# 03_POWER.net
KiCad netlist of a schematic drawn in Altium Designer
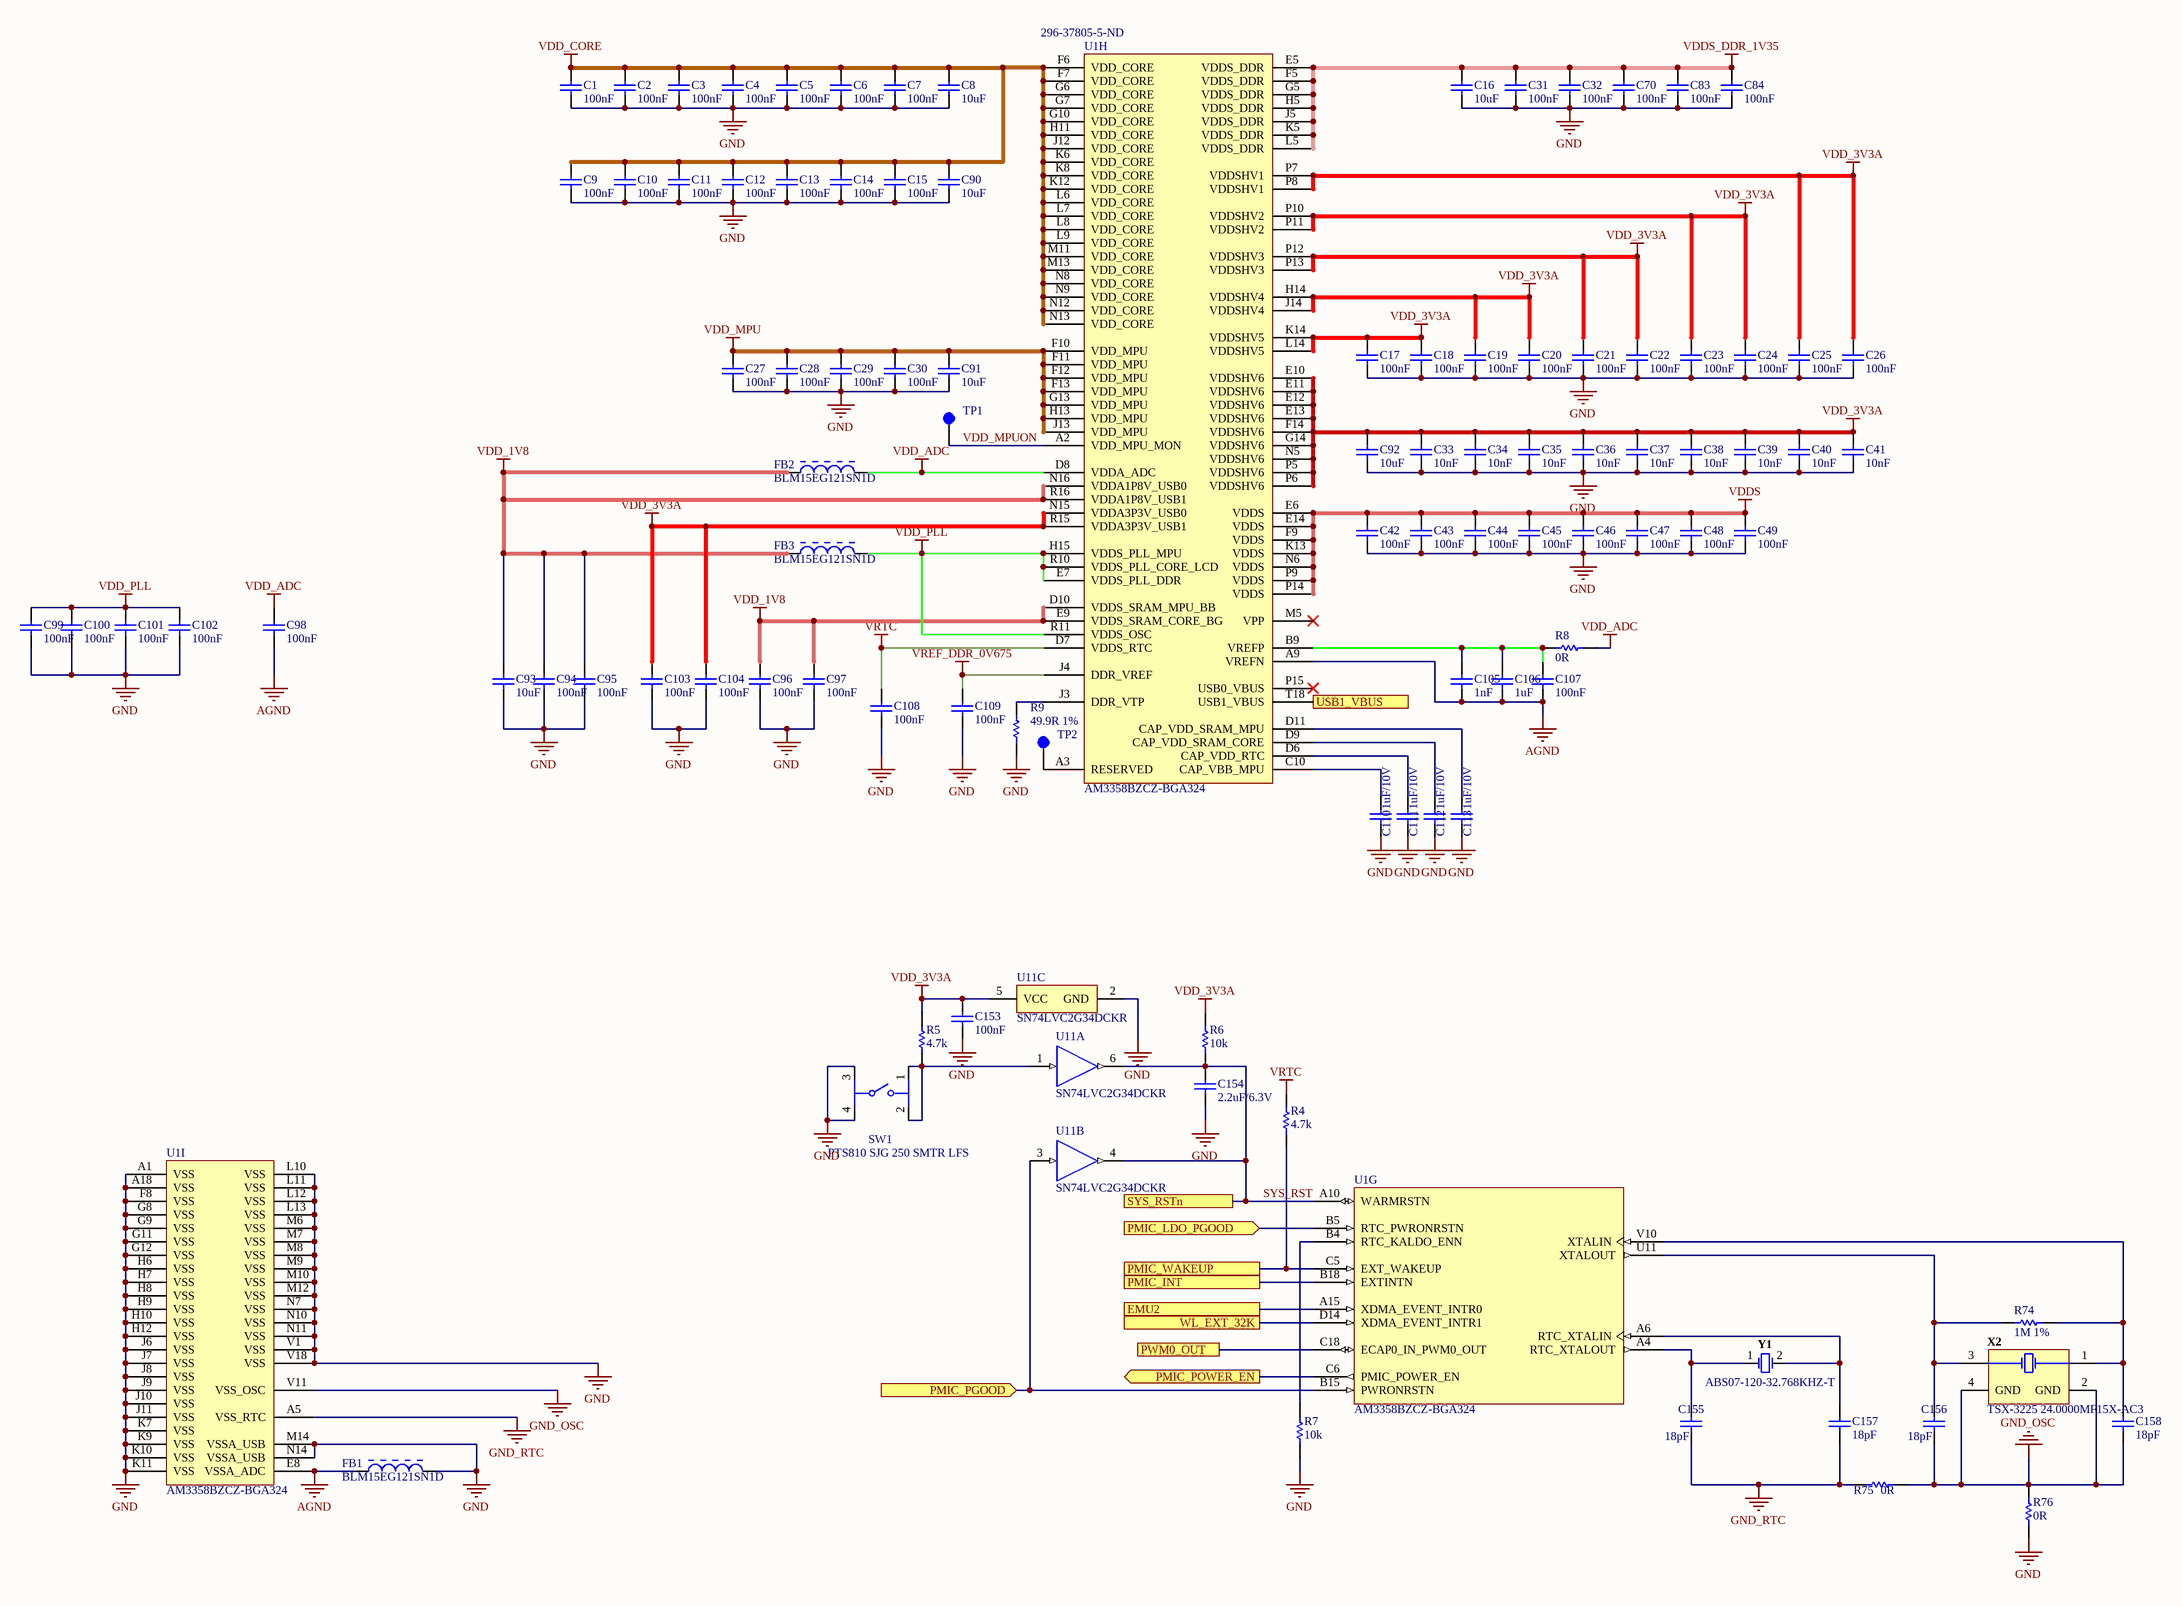
[diagram p0: 03. POWER.SchDoc]

(export (version "E")
  (design (tool "Eeschema 10.0.6"))
  (components
    (comp (ref "C1")
      (value "100nF")
      (footprint "CAPC1005X60X30LL05T10")
      (description "Chip Capacitor, 0.1 uF, +/- 10%, 16 V, -55 to 125 degC, 0402 (1005 Metric), RoHS, Tape and Reel")
      (fields (field (name "VOLTAGE") "16V") (field (name "TOLERANCE") "10%"))
      (libsource (lib "AM3358_DEV_BOARD") (part "CAP-NP-2"))
    )
    (comp (ref "C2")
      (value "100nF")
      (footprint "CAPC1005X60X30LL05T10")
      (description "Chip Capacitor, 0.1 uF, +/- 10%, 16 V, -55 to 125 degC, 0402 (1005 Metric), RoHS, Tape and Reel")
      (fields (field (name "VOLTAGE") "16V") (field (name "TOLERANCE") "10%"))
      (libsource (lib "AM3358_DEV_BOARD") (part "CAP-NP-2"))
    )
    (comp (ref "C3")
      (value "100nF")
      (footprint "CAPC1005X60X30LL05T10")
      (description "Chip Capacitor, 0.1 uF, +/- 10%, 16 V, -55 to 125 degC, 0402 (1005 Metric), RoHS, Tape and Reel")
      (fields (field (name "VOLTAGE") "16V") (field (name "TOLERANCE") "10%"))
      (libsource (lib "AM3358_DEV_BOARD") (part "CAP-NP-2"))
    )
    (comp (ref "C4")
      (value "100nF")
      (footprint "CAPC1005X60X30LL05T10")
      (description "Chip Capacitor, 0.1 uF, +/- 10%, 16 V, -55 to 125 degC, 0402 (1005 Metric), RoHS, Tape and Reel")
      (fields (field (name "VOLTAGE") "16V") (field (name "TOLERANCE") "10%"))
      (libsource (lib "AM3358_DEV_BOARD") (part "CAP-NP-2"))
    )
    (comp (ref "C5")
      (value "100nF")
      (footprint "CAPC1005X60X30LL05T10")
      (description "Chip Capacitor, 0.1 uF, +/- 10%, 16 V, -55 to 125 degC, 0402 (1005 Metric), RoHS, Tape and Reel")
      (fields (field (name "VOLTAGE") "16V") (field (name "TOLERANCE") "10%"))
      (libsource (lib "AM3358_DEV_BOARD") (part "CAP-NP-2"))
    )
    (comp (ref "C6")
      (value "100nF")
      (footprint "CAPC1005X60X30LL05T10")
      (description "Chip Capacitor, 0.1 uF, +/- 10%, 16 V, -55 to 125 degC, 0402 (1005 Metric), RoHS, Tape and Reel")
      (fields (field (name "VOLTAGE") "16V") (field (name "TOLERANCE") "10%"))
      (libsource (lib "AM3358_DEV_BOARD") (part "CAP-NP-2"))
    )
    (comp (ref "C7")
      (value "100nF")
      (footprint "CAPC1005X60X30LL05T10")
      (description "Chip Capacitor, 0.1 uF, +/- 10%, 16 V, -55 to 125 degC, 0402 (1005 Metric), RoHS, Tape and Reel")
      (fields (field (name "VOLTAGE") "16V") (field (name "TOLERANCE") "10%"))
      (libsource (lib "AM3358_DEV_BOARD") (part "CAP-NP-2"))
    )
    (comp (ref "C8")
      (value "10uF")
      (footprint "CAPC1005X60X30LL05T10")
      (fields (field (name "PART NUMBER") "GRM188R60J106ME47D") (field (name "MANUFACTURER") "Murata"))
      (libsource (lib "AM3358_DEV_BOARD") (part "CAP"))
    )
    (comp (ref "C9")
      (value "100nF")
      (footprint "CAPC1005X60X30LL05T10")
      (description "Chip Capacitor, 0.1 uF, +/- 10%, 16 V, -55 to 125 degC, 0402 (1005 Metric), RoHS, Tape and Reel")
      (fields (field (name "VOLTAGE") "16V") (field (name "TOLERANCE") "10%"))
      (libsource (lib "AM3358_DEV_BOARD") (part "CAP-NP-2"))
    )
    (comp (ref "C10")
      (value "100nF")
      (footprint "CAPC1005X60X30LL05T10")
      (description "Chip Capacitor, 0.1 uF, +/- 10%, 16 V, -55 to 125 degC, 0402 (1005 Metric), RoHS, Tape and Reel")
      (fields (field (name "VOLTAGE") "16V") (field (name "TOLERANCE") "10%"))
      (libsource (lib "AM3358_DEV_BOARD") (part "CAP-NP-2"))
    )
    (comp (ref "C11")
      (value "100nF")
      (footprint "CAPC1005X60X30LL05T10")
      (description "Chip Capacitor, 0.1 uF, +/- 10%, 16 V, -55 to 125 degC, 0402 (1005 Metric), RoHS, Tape and Reel")
      (fields (field (name "VOLTAGE") "16V") (field (name "TOLERANCE") "10%"))
      (libsource (lib "AM3358_DEV_BOARD") (part "CAP-NP-2"))
    )
    (comp (ref "C12")
      (value "100nF")
      (footprint "CAPC1005X60X30LL05T10")
      (description "Chip Capacitor, 0.1 uF, +/- 10%, 16 V, -55 to 125 degC, 0402 (1005 Metric), RoHS, Tape and Reel")
      (fields (field (name "VOLTAGE") "16V") (field (name "TOLERANCE") "10%"))
      (libsource (lib "AM3358_DEV_BOARD") (part "CAP-NP-2"))
    )
    (comp (ref "C13")
      (value "100nF")
      (footprint "CAPC1005X60X30LL05T10")
      (description "Chip Capacitor, 0.1 uF, +/- 10%, 16 V, -55 to 125 degC, 0402 (1005 Metric), RoHS, Tape and Reel")
      (fields (field (name "VOLTAGE") "16V") (field (name "TOLERANCE") "10%"))
      (libsource (lib "AM3358_DEV_BOARD") (part "CAP-NP-2"))
    )
    (comp (ref "C14")
      (value "100nF")
      (footprint "CAPC1005X60X30LL05T10")
      (description "Chip Capacitor, 0.1 uF, +/- 10%, 16 V, -55 to 125 degC, 0402 (1005 Metric), RoHS, Tape and Reel")
      (fields (field (name "VOLTAGE") "16V") (field (name "TOLERANCE") "10%"))
      (libsource (lib "AM3358_DEV_BOARD") (part "CAP-NP-2"))
    )
    (comp (ref "C15")
      (value "100nF")
      (footprint "CAPC1005X60X30LL05T10")
      (description "Chip Capacitor, 0.1 uF, +/- 10%, 16 V, -55 to 125 degC, 0402 (1005 Metric), RoHS, Tape and Reel")
      (fields (field (name "VOLTAGE") "16V") (field (name "TOLERANCE") "10%"))
      (libsource (lib "AM3358_DEV_BOARD") (part "CAP-NP-2"))
    )
    (comp (ref "C16")
      (value "10uF")
      (footprint "CAPC1608X90X35NL10T15")
      (fields (field (name "PART NUMBER") "GRM188R60J106ME47D") (field (name "MANUFACTURER") "Murata"))
      (libsource (lib "Altium Content Vault") (part "CAP"))
    )
    (comp (ref "C17")
      (value "100nF")
      (footprint "CAPC1005X60X30LL05T10")
      (description "Chip Capacitor, 0.1 uF, +/- 10%, 16 V, -55 to 125 degC, 0402 (1005 Metric), RoHS, Tape and Reel")
      (fields (field (name "VOLTAGE") "16V") (field (name "TOLERANCE") "10%"))
      (libsource (lib "AM3358_DEV_BOARD") (part "CAP-NP-2"))
    )
    (comp (ref "C18")
      (value "100nF")
      (footprint "CAPC1005X60X30LL05T10")
      (description "Chip Capacitor, 0.1 uF, +/- 10%, 16 V, -55 to 125 degC, 0402 (1005 Metric), RoHS, Tape and Reel")
      (fields (field (name "VOLTAGE") "16V") (field (name "TOLERANCE") "10%"))
      (libsource (lib "AM3358_DEV_BOARD") (part "CAP-NP-2"))
    )
    (comp (ref "C19")
      (value "100nF")
      (footprint "CAPC1005X60X30LL05T10")
      (description "Chip Capacitor, 0.1 uF, +/- 10%, 16 V, -55 to 125 degC, 0402 (1005 Metric), RoHS, Tape and Reel")
      (fields (field (name "VOLTAGE") "16V") (field (name "TOLERANCE") "10%"))
      (libsource (lib "AM3358_DEV_BOARD") (part "CAP-NP-2"))
    )
    (comp (ref "C20")
      (value "100nF")
      (footprint "CAPC1005X60X30LL05T10")
      (description "Chip Capacitor, 0.1 uF, +/- 10%, 16 V, -55 to 125 degC, 0402 (1005 Metric), RoHS, Tape and Reel")
      (fields (field (name "VOLTAGE") "16V") (field (name "TOLERANCE") "10%"))
      (libsource (lib "AM3358_DEV_BOARD") (part "CAP-NP-2"))
    )
    (comp (ref "C21")
      (value "100nF")
      (footprint "CAPC1005X60X30LL05T10")
      (description "Chip Capacitor, 0.1 uF, +/- 10%, 16 V, -55 to 125 degC, 0402 (1005 Metric), RoHS, Tape and Reel")
      (fields (field (name "VOLTAGE") "16V") (field (name "TOLERANCE") "10%"))
      (libsource (lib "AM3358_DEV_BOARD") (part "CAP-NP-2"))
    )
    (comp (ref "C22")
      (value "100nF")
      (footprint "CAPC1005X60X30LL05T10")
      (description "Chip Capacitor, 0.1 uF, +/- 10%, 16 V, -55 to 125 degC, 0402 (1005 Metric), RoHS, Tape and Reel")
      (fields (field (name "VOLTAGE") "16V") (field (name "TOLERANCE") "10%"))
      (libsource (lib "AM3358_DEV_BOARD") (part "CAP-NP-2"))
    )
    (comp (ref "C23")
      (value "100nF")
      (footprint "CAPC1005X60X30LL05T10")
      (description "Chip Capacitor, 0.1 uF, +/- 10%, 16 V, -55 to 125 degC, 0402 (1005 Metric), RoHS, Tape and Reel")
      (fields (field (name "VOLTAGE") "16V") (field (name "TOLERANCE") "10%"))
      (libsource (lib "AM3358_DEV_BOARD") (part "CAP-NP-2"))
    )
    (comp (ref "C24")
      (value "100nF")
      (footprint "CAPC1005X60X30LL05T10")
      (description "Chip Capacitor, 0.1 uF, +/- 10%, 16 V, -55 to 125 degC, 0402 (1005 Metric), RoHS, Tape and Reel")
      (fields (field (name "VOLTAGE") "16V") (field (name "TOLERANCE") "10%"))
      (libsource (lib "AM3358_DEV_BOARD") (part "CAP-NP-2"))
    )
    (comp (ref "C25")
      (value "100nF")
      (footprint "CAPC1005X60X30LL05T10")
      (description "Chip Capacitor, 0.1 uF, +/- 10%, 16 V, -55 to 125 degC, 0402 (1005 Metric), RoHS, Tape and Reel")
      (fields (field (name "VOLTAGE") "16V") (field (name "TOLERANCE") "10%"))
      (libsource (lib "AM3358_DEV_BOARD") (part "CAP-NP-2"))
    )
    (comp (ref "C26")
      (value "100nF")
      (footprint "CAPC1005X60X30LL05T10")
      (description "Chip Capacitor, 0.1 uF, +/- 10%, 16 V, -55 to 125 degC, 0402 (1005 Metric), RoHS, Tape and Reel")
      (fields (field (name "VOLTAGE") "16V") (field (name "TOLERANCE") "10%"))
      (libsource (lib "AM3358_DEV_BOARD") (part "CAP-NP-2"))
    )
    (comp (ref "C27")
      (value "100nF")
      (footprint "CAPC1005X60X30LL05T10")
      (description "Chip Capacitor, 0.1 uF, +/- 10%, 16 V, -55 to 125 degC, 0402 (1005 Metric), RoHS, Tape and Reel")
      (fields (field (name "VOLTAGE") "16V") (field (name "TOLERANCE") "10%"))
      (libsource (lib "AM3358_DEV_BOARD") (part "CAP-NP-2"))
    )
    (comp (ref "C28")
      (value "100nF")
      (footprint "CAPC1005X60X30LL05T10")
      (description "Chip Capacitor, 0.1 uF, +/- 10%, 16 V, -55 to 125 degC, 0402 (1005 Metric), RoHS, Tape and Reel")
      (fields (field (name "VOLTAGE") "16V") (field (name "TOLERANCE") "10%"))
      (libsource (lib "AM3358_DEV_BOARD") (part "CAP-NP-2"))
    )
    (comp (ref "C29")
      (value "100nF")
      (footprint "CAPC1005X60X30LL05T10")
      (description "Chip Capacitor, 0.1 uF, +/- 10%, 16 V, -55 to 125 degC, 0402 (1005 Metric), RoHS, Tape and Reel")
      (fields (field (name "VOLTAGE") "16V") (field (name "TOLERANCE") "10%"))
      (libsource (lib "AM3358_DEV_BOARD") (part "CAP-NP-2"))
    )
    (comp (ref "C30")
      (value "100nF")
      (footprint "CAPC1005X60X30LL05T10")
      (description "Chip Capacitor, 0.1 uF, +/- 10%, 16 V, -55 to 125 degC, 0402 (1005 Metric), RoHS, Tape and Reel")
      (fields (field (name "VOLTAGE") "16V") (field (name "TOLERANCE") "10%"))
      (libsource (lib "AM3358_DEV_BOARD") (part "CAP-NP-2"))
    )
    (comp (ref "C31")
      (value "100nF")
      (footprint "CAPC1005X60X30LL05T10")
      (description "Chip Capacitor, 0.1 uF, +/- 10%, 16 V, -55 to 125 degC, 0402 (1005 Metric), RoHS, Tape and Reel")
      (fields (field (name "VOLTAGE") "16V") (field (name "TOLERANCE") "10%"))
      (libsource (lib "AM3358_DEV_BOARD") (part "CAP-NP-2"))
    )
    (comp (ref "C32")
      (value "100nF")
      (footprint "CAPC1005X60X30LL05T10")
      (description "Chip Capacitor, 0.1 uF, +/- 10%, 16 V, -55 to 125 degC, 0402 (1005 Metric), RoHS, Tape and Reel")
      (fields (field (name "VOLTAGE") "16V") (field (name "TOLERANCE") "10%"))
      (libsource (lib "AM3358_DEV_BOARD") (part "CAP-NP-2"))
    )
    (comp (ref "C33")
      (value "10nF")
      (footprint "CAPC1005X60X30LL05T10")
      (description "Chip Capacitor, 0.1 uF, +/- 10%, 16 V, -55 to 125 degC, 0402 (1005 Metric), RoHS, Tape and Reel")
      (fields (field (name "VOLTAGE") "16V") (field (name "TOLERANCE") "10%"))
      (libsource (lib "AM3358_DEV_BOARD") (part "CAP-NP-2"))
    )
    (comp (ref "C34")
      (value "10nF")
      (footprint "CAPC1005X60X30LL05T10")
      (description "Chip Capacitor, 0.1 uF, +/- 10%, 16 V, -55 to 125 degC, 0402 (1005 Metric), RoHS, Tape and Reel")
      (fields (field (name "VOLTAGE") "16V") (field (name "TOLERANCE") "10%"))
      (libsource (lib "AM3358_DEV_BOARD") (part "CAP-NP-2"))
    )
    (comp (ref "C35")
      (value "10nF")
      (footprint "CAPC1005X60X30LL05T10")
      (description "Chip Capacitor, 0.1 uF, +/- 10%, 16 V, -55 to 125 degC, 0402 (1005 Metric), RoHS, Tape and Reel")
      (fields (field (name "VOLTAGE") "16V") (field (name "TOLERANCE") "10%"))
      (libsource (lib "AM3358_DEV_BOARD") (part "CAP-NP-2"))
    )
    (comp (ref "C36")
      (value "10nF")
      (footprint "CAPC1005X60X30LL05T10")
      (description "Chip Capacitor, 0.1 uF, +/- 10%, 16 V, -55 to 125 degC, 0402 (1005 Metric), RoHS, Tape and Reel")
      (fields (field (name "VOLTAGE") "16V") (field (name "TOLERANCE") "10%"))
      (libsource (lib "AM3358_DEV_BOARD") (part "CAP-NP-2"))
    )
    (comp (ref "C37")
      (value "10nF")
      (footprint "CAPC1005X60X30LL05T10")
      (description "Chip Capacitor, 0.1 uF, +/- 10%, 16 V, -55 to 125 degC, 0402 (1005 Metric), RoHS, Tape and Reel")
      (fields (field (name "VOLTAGE") "16V") (field (name "TOLERANCE") "10%"))
      (libsource (lib "AM3358_DEV_BOARD") (part "CAP-NP-2"))
    )
    (comp (ref "C38")
      (value "10nF")
      (footprint "CAPC1005X60X30LL05T10")
      (description "Chip Capacitor, 0.1 uF, +/- 10%, 16 V, -55 to 125 degC, 0402 (1005 Metric), RoHS, Tape and Reel")
      (fields (field (name "VOLTAGE") "16V") (field (name "TOLERANCE") "10%"))
      (libsource (lib "AM3358_DEV_BOARD") (part "CAP-NP-2"))
    )
    (comp (ref "C39")
      (value "10nF")
      (footprint "CAPC1005X60X30LL05T10")
      (description "Chip Capacitor, 0.1 uF, +/- 10%, 16 V, -55 to 125 degC, 0402 (1005 Metric), RoHS, Tape and Reel")
      (fields (field (name "VOLTAGE") "16V") (field (name "TOLERANCE") "10%"))
      (libsource (lib "AM3358_DEV_BOARD") (part "CAP-NP-2"))
    )
    (comp (ref "C40")
      (value "10nF")
      (footprint "CAPC1005X60X30LL05T10")
      (description "Chip Capacitor, 0.1 uF, +/- 10%, 16 V, -55 to 125 degC, 0402 (1005 Metric), RoHS, Tape and Reel")
      (fields (field (name "VOLTAGE") "16V") (field (name "TOLERANCE") "10%"))
      (libsource (lib "AM3358_DEV_BOARD") (part "CAP-NP-2"))
    )
    (comp (ref "C41")
      (value "10nF")
      (footprint "CAPC1005X60X30LL05T10")
      (description "Chip Capacitor, 0.1 uF, +/- 10%, 16 V, -55 to 125 degC, 0402 (1005 Metric), RoHS, Tape and Reel")
      (fields (field (name "VOLTAGE") "16V") (field (name "TOLERANCE") "10%"))
      (libsource (lib "AM3358_DEV_BOARD") (part "CAP-NP-2"))
    )
    (comp (ref "C42")
      (value "100nF")
      (footprint "CAPC1005X60X30LL05T10")
      (description "Chip Capacitor, 0.1 uF, +/- 10%, 16 V, -55 to 125 degC, 0402 (1005 Metric), RoHS, Tape and Reel")
      (fields (field (name "VOLTAGE") "16V") (field (name "TOLERANCE") "10%"))
      (libsource (lib "AM3358_DEV_BOARD") (part "CAP-NP-2"))
    )
    (comp (ref "C43")
      (value "100nF")
      (footprint "CAPC1005X60X30LL05T10")
      (description "Chip Capacitor, 0.1 uF, +/- 10%, 16 V, -55 to 125 degC, 0402 (1005 Metric), RoHS, Tape and Reel")
      (fields (field (name "VOLTAGE") "16V") (field (name "TOLERANCE") "10%"))
      (libsource (lib "AM3358_DEV_BOARD") (part "CAP-NP-2"))
    )
    (comp (ref "C44")
      (value "100nF")
      (footprint "CAPC1005X60X30LL05T10")
      (description "Chip Capacitor, 0.1 uF, +/- 10%, 16 V, -55 to 125 degC, 0402 (1005 Metric), RoHS, Tape and Reel")
      (fields (field (name "VOLTAGE") "16V") (field (name "TOLERANCE") "10%"))
      (libsource (lib "AM3358_DEV_BOARD") (part "CAP-NP-2"))
    )
    (comp (ref "C45")
      (value "100nF")
      (footprint "CAPC1005X60X30LL05T10")
      (description "Chip Capacitor, 0.1 uF, +/- 10%, 16 V, -55 to 125 degC, 0402 (1005 Metric), RoHS, Tape and Reel")
      (fields (field (name "VOLTAGE") "16V") (field (name "TOLERANCE") "10%"))
      (libsource (lib "AM3358_DEV_BOARD") (part "CAP-NP-2"))
    )
    (comp (ref "C46")
      (value "100nF")
      (footprint "CAPC1005X60X30LL05T10")
      (description "Chip Capacitor, 0.1 uF, +/- 10%, 16 V, -55 to 125 degC, 0402 (1005 Metric), RoHS, Tape and Reel")
      (fields (field (name "VOLTAGE") "16V") (field (name "TOLERANCE") "10%"))
      (libsource (lib "AM3358_DEV_BOARD") (part "CAP-NP-2"))
    )
    (comp (ref "C47")
      (value "100nF")
      (footprint "CAPC1005X60X30LL05T10")
      (description "Chip Capacitor, 0.1 uF, +/- 10%, 16 V, -55 to 125 degC, 0402 (1005 Metric), RoHS, Tape and Reel")
      (fields (field (name "VOLTAGE") "16V") (field (name "TOLERANCE") "10%"))
      (libsource (lib "AM3358_DEV_BOARD") (part "CAP-NP-2"))
    )
    (comp (ref "C48")
      (value "100nF")
      (footprint "CAPC1005X60X30LL05T10")
      (description "Chip Capacitor, 0.1 uF, +/- 10%, 16 V, -55 to 125 degC, 0402 (1005 Metric), RoHS, Tape and Reel")
      (fields (field (name "VOLTAGE") "16V") (field (name "TOLERANCE") "10%"))
      (libsource (lib "AM3358_DEV_BOARD") (part "CAP-NP-2"))
    )
    (comp (ref "C49")
      (value "100nF")
      (footprint "CAPC1005X60X30LL05T10")
      (description "Chip Capacitor, 0.1 uF, +/- 10%, 16 V, -55 to 125 degC, 0402 (1005 Metric), RoHS, Tape and Reel")
      (fields (field (name "VOLTAGE") "16V") (field (name "TOLERANCE") "10%"))
      (libsource (lib "AM3358_DEV_BOARD") (part "CAP-NP-2"))
    )
    (comp (ref "C70")
      (value "100nF")
      (footprint "CAPC1005X60X30LL05T10")
      (description "Chip Capacitor, 0.1 uF, +/- 10%, 16 V, -55 to 125 degC, 0402 (1005 Metric), RoHS, Tape and Reel")
      (fields (field (name "VOLTAGE") "16V") (field (name "TOLERANCE") "10%"))
      (libsource (lib "AM3358_DEV_BOARD") (part "CAP-NP-2"))
    )
    (comp (ref "C83")
      (value "100nF")
      (footprint "CAPC1005X60X30LL05T10")
      (description "Chip Capacitor, 0.1 uF, +/- 10%, 16 V, -55 to 125 degC, 0402 (1005 Metric), RoHS, Tape and Reel")
      (fields (field (name "VOLTAGE") "16V") (field (name "TOLERANCE") "10%"))
      (libsource (lib "AM3358_DEV_BOARD") (part "CAP-NP-2"))
    )
    (comp (ref "C84")
      (value "100nF")
      (footprint "CAPC1005X60X30LL05T10")
      (description "Chip Capacitor, 0.1 uF, +/- 10%, 16 V, -55 to 125 degC, 0402 (1005 Metric), RoHS, Tape and Reel")
      (fields (field (name "VOLTAGE") "16V") (field (name "TOLERANCE") "10%"))
      (libsource (lib "AM3358_DEV_BOARD") (part "CAP-NP-2"))
    )
    (comp (ref "C90")
      (value "10uF")
      (footprint "CAPC1005X60X30LL05T10")
      (fields (field (name "PART NUMBER") "GRM188R60J106ME47D") (field (name "MANUFACTURER") "Murata"))
      (libsource (lib "AM3358_DEV_BOARD") (part "CAP"))
    )
    (comp (ref "C91")
      (value "10uF")
      (footprint "RESC1005X40X25LL05T05")
      (fields (field (name "PART NUMBER") "GRM188R60J106ME47D") (field (name "MANUFACTURER") "Murata"))
      (libsource (lib "AM3358_DEV_BOARD") (part "CAP"))
    )
    (comp (ref "C92")
      (value "10uF")
      (footprint "CAPC1608X90X35NL10T15")
      (fields (field (name "PART NUMBER") "GRM188R60J106ME47D") (field (name "MANUFACTURER") "Murata"))
      (libsource (lib "Altium Content Vault") (part "CAP"))
    )
    (comp (ref "C93")
      (value "10uF")
      (footprint "CAPC1608X90X35NL10T15")
      (fields (field (name "PART NUMBER") "GRM188R60J106ME47D") (field (name "MANUFACTURER") "Murata"))
      (libsource (lib "Altium Content Vault") (part "CAP"))
    )
    (comp (ref "C94")
      (value "100nF")
      (footprint "CAPC1005X60X30LL05T10")
      (description "Chip Capacitor, 0.1 uF, +/- 10%, 16 V, -55 to 125 degC, 0402 (1005 Metric), RoHS, Tape and Reel")
      (fields (field (name "VOLTAGE") "16V") (field (name "TOLERANCE") "10%"))
      (libsource (lib "AM3358_DEV_BOARD") (part "CAP-NP-2"))
    )
    (comp (ref "C95")
      (value "100nF")
      (footprint "CAPC1005X60X30LL05T10")
      (description "Chip Capacitor, 0.1 uF, +/- 10%, 16 V, -55 to 125 degC, 0402 (1005 Metric), RoHS, Tape and Reel")
      (fields (field (name "VOLTAGE") "16V") (field (name "TOLERANCE") "10%"))
      (libsource (lib "AM3358_DEV_BOARD") (part "CAP-NP-2"))
    )
    (comp (ref "C96")
      (value "100nF")
      (footprint "CAPC1005X60X30LL05T10")
      (description "Chip Capacitor, 0.1 uF, +/- 10%, 16 V, -55 to 125 degC, 0402 (1005 Metric), RoHS, Tape and Reel")
      (fields (field (name "VOLTAGE") "16V") (field (name "TOLERANCE") "10%"))
      (libsource (lib "AM3358_DEV_BOARD") (part "CAP-NP-2"))
    )
    (comp (ref "C97")
      (value "100nF")
      (footprint "CAPC1005X60X30LL05T10")
      (description "Chip Capacitor, 0.1 uF, +/- 10%, 16 V, -55 to 125 degC, 0402 (1005 Metric), RoHS, Tape and Reel")
      (fields (field (name "VOLTAGE") "16V") (field (name "TOLERANCE") "10%"))
      (libsource (lib "AM3358_DEV_BOARD") (part "CAP-NP-2"))
    )
    (comp (ref "C98")
      (value "100nF")
      (footprint "RESC1005X40X25LL05T05")
      (description "Chip Capacitor, 0.1 uF, +/- 10%, 16 V, -55 to 125 degC, 0402 (1005 Metric), RoHS, Tape and Reel")
      (fields (field (name "VOLTAGE") "16V") (field (name "TOLERANCE") "10%"))
      (libsource (lib "AM3358_DEV_BOARD") (part "CAP-NP-2"))
    )
    (comp (ref "C99")
      (value "100nF")
      (footprint "RESC1005X40X25LL05T05")
      (description "Chip Capacitor, 0.1 uF, +/- 10%, 16 V, -55 to 125 degC, 0402 (1005 Metric), RoHS, Tape and Reel")
      (fields (field (name "VOLTAGE") "16V") (field (name "TOLERANCE") "10%"))
      (libsource (lib "AM3358_DEV_BOARD") (part "CAP-NP-2"))
    )
    (comp (ref "C100")
      (value "100nF")
      (footprint "RESC1005X40X25LL05T05")
      (description "Chip Capacitor, 0.1 uF, +/- 10%, 16 V, -55 to 125 degC, 0402 (1005 Metric), RoHS, Tape and Reel")
      (fields (field (name "VOLTAGE") "16V") (field (name "TOLERANCE") "10%"))
      (libsource (lib "AM3358_DEV_BOARD") (part "CAP-NP-2"))
    )
    (comp (ref "C101")
      (value "100nF")
      (footprint "RESC1005X40X25LL05T05")
      (description "Chip Capacitor, 0.1 uF, +/- 10%, 16 V, -55 to 125 degC, 0402 (1005 Metric), RoHS, Tape and Reel")
      (fields (field (name "VOLTAGE") "16V") (field (name "TOLERANCE") "10%"))
      (libsource (lib "AM3358_DEV_BOARD") (part "CAP-NP-2"))
    )
    (comp (ref "C102")
      (value "100nF")
      (footprint "RESC1005X40X25LL05T05")
      (description "Chip Capacitor, 0.1 uF, +/- 10%, 16 V, -55 to 125 degC, 0402 (1005 Metric), RoHS, Tape and Reel")
      (fields (field (name "VOLTAGE") "16V") (field (name "TOLERANCE") "10%"))
      (libsource (lib "AM3358_DEV_BOARD") (part "CAP-NP-2"))
    )
    (comp (ref "C103")
      (value "100nF")
      (footprint "CAPC1005X60X30LL05T10")
      (description "Chip Capacitor, 0.1 uF, +/- 10%, 16 V, -55 to 125 degC, 0402 (1005 Metric), RoHS, Tape and Reel")
      (fields (field (name "VOLTAGE") "16V") (field (name "TOLERANCE") "10%"))
      (libsource (lib "AM3358_DEV_BOARD") (part "CAP-NP-2"))
    )
    (comp (ref "C104")
      (value "100nF")
      (footprint "CAPC1005X60X30LL05T10")
      (description "Chip Capacitor, 0.1 uF, +/- 10%, 16 V, -55 to 125 degC, 0402 (1005 Metric), RoHS, Tape and Reel")
      (fields (field (name "VOLTAGE") "16V") (field (name "TOLERANCE") "10%"))
      (libsource (lib "AM3358_DEV_BOARD") (part "CAP-NP-2"))
    )
    (comp (ref "C105")
      (value "1nF")
      (footprint "CAPC1005X60X30LL05T10")
      (fields (field (name "PART NUMBER") "GRM1555C1H102JA01D") (field (name "MANUFACTURER") "Murata"))
      (libsource (lib "AM3358_DEV_BOARD") (part "CAP"))
    )
    (comp (ref "C106")
      (value "1uF")
      (footprint "CAPC1005X55X25NL05T10")
      (fields (field (name "PART NUMBER") "GRM155R61A105KE15D") (field (name "MANUFACTURER") "Murata"))
      (libsource (lib "Altium Content Vault") (part "CAP"))
    )
    (comp (ref "C107")
      (value "100nF")
      (footprint "CAPC1005X60X30LL05T10")
      (description "Chip Capacitor, 0.1 uF, +/- 10%, 16 V, -55 to 125 degC, 0402 (1005 Metric), RoHS, Tape and Reel")
      (fields (field (name "VOLTAGE") "16V") (field (name "TOLERANCE") "10%"))
      (libsource (lib "AM3358_DEV_BOARD") (part "CAP-NP-2"))
    )
    (comp (ref "C108")
      (value "100nF")
      (footprint "CAPC1005X60X30LL05T10")
      (description "Chip Capacitor, 0.1 uF, +/- 10%, 16 V, -55 to 125 degC, 0402 (1005 Metric), RoHS, Tape and Reel")
      (fields (field (name "VOLTAGE") "16V") (field (name "TOLERANCE") "10%"))
      (libsource (lib "AM3358_DEV_BOARD") (part "CAP-NP-2"))
    )
    (comp (ref "C109")
      (value "100nF")
      (footprint "CAPC1005X60X30LL05T10")
      (description "Chip Capacitor, 0.1 uF, +/- 10%, 16 V, -55 to 125 degC, 0402 (1005 Metric), RoHS, Tape and Reel")
      (fields (field (name "VOLTAGE") "16V") (field (name "TOLERANCE") "10%"))
      (libsource (lib "AM3358_DEV_BOARD") (part "CAP-NP-2"))
    )
    (comp (ref "C110")
      (value "1uF/10V")
      (footprint "CAPC1005X55X25NL05T10")
      (fields (field (name "PART NUMBER") "GRM155R61A105KE15D") (field (name "MANUFACTURER") "Murata"))
      (libsource (lib "Altium Content Vault") (part "CAP"))
    )
    (comp (ref "C111")
      (value "1uF/10V")
      (footprint "CAPC1005X55X25NL05T10")
      (fields (field (name "PART NUMBER") "GRM155R61A105KE15D") (field (name "MANUFACTURER") "Murata"))
      (libsource (lib "Altium Content Vault") (part "CAP"))
    )
    (comp (ref "C112")
      (value "1uF/10V")
      (footprint "CAPC1005X55X25NL05T10")
      (fields (field (name "PART NUMBER") "GRM155R61A105KE15D") (field (name "MANUFACTURER") "Murata"))
      (libsource (lib "Altium Content Vault") (part "CAP"))
    )
    (comp (ref "C113")
      (value "1uF/10V")
      (footprint "CAPC1005X55X25NL05T10")
      (fields (field (name "PART NUMBER") "GRM155R61A105KE15D") (field (name "MANUFACTURER") "Murata"))
      (libsource (lib "Altium Content Vault") (part "CAP"))
    )
    (comp (ref "C153")
      (value "100nF")
      (footprint "CAPC1005X55X25LL05T10")
      (description "Chip Capacitor, 0.1 uF, +/- 10%, 16 V, -55 to 125 degC, 0402 (1005 Metric), RoHS, Tape and Reel")
      (fields (field (name "VOLTAGE") "16V") (field (name "TOLERANCE") "10%"))
      (libsource (lib "Altium Content Vault") (part "CAP-NP-2"))
    )
    (comp (ref "C154")
      (value "2.2uF/6.3V")
      (footprint "CAPC1005X60X30LL05T10")
      (fields (field (name "MANUFACTURER") "Kemet") (field (name "PART NUMBER") "C0402C225M9PAC7867"))
      (libsource (lib "Altium Content Vault") (part "CAP"))
    )
    (comp (ref "C155")
      (value "18pF")
      (footprint "CAPC1005X60X30LL05T10")
      (fields (field (name "PART NUMBER") "GRM1555C1H180JA01D") (field (name "MANUFACTURER") "Murata"))
      (libsource (lib "AM3358_DEV_BOARD") (part "CAP"))
    )
    (comp (ref "C156")
      (value "18pF")
      (footprint "CAPC1005X60X30LL05T10")
      (fields (field (name "PART NUMBER") "GRM1555C1H180JA01D") (field (name "MANUFACTURER") "Murata"))
      (libsource (lib "AM3358_DEV_BOARD") (part "CAP"))
    )
    (comp (ref "C157")
      (value "18pF")
      (footprint "CAPC1005X60X30LL05T10")
      (fields (field (name "PART NUMBER") "GRM1555C1H180JA01D") (field (name "MANUFACTURER") "Murata"))
      (libsource (lib "AM3358_DEV_BOARD") (part "CAP"))
    )
    (comp (ref "C158")
      (value "18pF")
      (footprint "CAPC1005X60X30LL05T10")
      (fields (field (name "PART NUMBER") "GRM1555C1H180JA01D") (field (name "MANUFACTURER") "Murata"))
      (libsource (lib "AM3358_DEV_BOARD") (part "CAP"))
    )
    (comp (ref "FB1")
      (value "BLM15EG121SN1D")
      (footprint "MURA-BLM15-CHIP-2_V")
      (fields (field (name "MANUFACTURER") "Murata"))
      (libsource (lib "Altium Content Vault") (part "MURA-FB-2"))
    )
    (comp (ref "FB2")
      (value "BLM15EG121SN1D")
      (footprint "MURA-BLM15-CHIP-2_V")
      (fields (field (name "MANUFACTURER") "Murata"))
      (libsource (lib "Altium Content Vault") (part "MURA-FB-2"))
    )
    (comp (ref "FB3")
      (value "BLM15EG121SN1D")
      (footprint "MURA-BLM15-CHIP-2_V")
      (fields (field (name "MANUFACTURER") "Murata"))
      (libsource (lib "Altium Content Vault") (part "MURA-FB-2"))
    )
    (comp (ref "R4")
      (value "4.7k")
      (footprint "RESC1005X40X25LL05T05")
      (fields (field (name "PART NUMBER") "RC0402FR-134K7L") (field (name "MANUFACTURER") "Yageo"))
      (libsource (lib "AM3358_DEV_BOARD") (part "RES"))
    )
    (comp (ref "R5")
      (value "4.7k")
      (footprint "RESC1005X40X25LL05T05")
      (fields (field (name "PART NUMBER") "RC0402FR-134K7L") (field (name "MANUFACTURER") "Yageo"))
      (libsource (lib "AM3358_DEV_BOARD") (part "RES"))
    )
    (comp (ref "R6")
      (value "10k")
      (footprint "RESC1005X40X25LL05T05")
      (fields (field (name "MANUFACTURER") "Vishay Dale") (field (name "PART NUMBER") "CRCW040210K0FKED"))
      (libsource (lib "AM3358_DEV_BOARD") (part "RES"))
    )
    (comp (ref "R7")
      (value "10k")
      (footprint "RESC1005X40X25LL05T05")
      (fields (field (name "MANUFACTURER") "Vishay Dale") (field (name "PART NUMBER") "CRCW040210K0FKED"))
      (libsource (lib "AM3358_DEV_BOARD") (part "RES"))
    )
    (comp (ref "R8")
      (value "0R")
      (footprint "RESC1005X40X25LL05T05")
      (fields (field (name "MANUFACTURER") "Yageo / Phycomp") (field (name "PART NUMBER") "RC0402JR-070RL"))
      (libsource (lib "AM3358_DEV_BOARD") (part "RES"))
    )
    (comp (ref "R9")
      (value "49.9R 1%")
      (footprint "RESC1005X40X25LL05T05")
      (description "Precision Thick Film Chip Resistors")
      (fields (field (name "MANUFACTURER") "Panasonic") (field (name "PART NUMBER") "ERJ-2RKF49R9X"))
      (libsource (lib "AM3358_DEV_BOARD") (part "RES"))
    )
    (comp (ref "R74")
      (value "1M 1%")
      (footprint "RESC1005X40X25LL05T05")
      (description "Chip Resistor, 1 MOhm, +/- 1%, 100 mW, -55 to 155 degC, 0402 (1005 Metric), RoHS, Tape and Reel")
      (fields (field (name "PARTNUMBER") "ERJ-2RKF1004X") (field (name "TOLERANCE") "1%"))
      (libsource (lib "AM3358_DEV_BOARD") (part "RES-2"))
    )
    (comp (ref "R75")
      (value "0R")
      (footprint "RESC1005X40X25LL05T05")
      (fields (field (name "MANUFACTURER") "Yageo / Phycomp") (field (name "PART NUMBER") "RC0402JR-070RL"))
      (libsource (lib "AM3358_DEV_BOARD") (part "RES"))
    )
    (comp (ref "R76")
      (value "0R")
      (footprint "RESC1005X40X25LL05T05")
      (fields (field (name "MANUFACTURER") "Yageo / Phycomp") (field (name "PART NUMBER") "RC0402JR-070RL"))
      (libsource (lib "AM3358_DEV_BOARD") (part "RES"))
    )
    (comp (ref "SW1")
      (value "PTS810 SJG 250 SMTR LFS")
      (footprint "FP-PTS810_SJG_250_SMTR_LF-MFG")
      (description "SWITCH TACTILE SPST-NO 0.05A 16V")
      (fields
        (field (name "MANUFACTURER") "C&K Components")
        (field (name "OCTOPART") "https://octopart.com/pts810sjg250smtrlfs-c%26k+components-29380277")
      )
      (libsource (lib "Altium Content Vault") (part "1adf0dd01260c80cf25a44bfd6b99ba"))
    )
    (comp (ref "TP1") (value "Test Point") (footprint "TP") (libsource (lib "SyTungNguyen") (part "TP")))
    (comp (ref "TP2") (value "Test Point") (footprint "TP") (libsource (lib "SyTungNguyen") (part "TP")))
    (comp (ref "U1")
      (value "AM3358BZCZ-BGA324")
      (footprint "TI-ZCZ324")
      (fields (field (name "SUPPLIER PART NUMBER 1") "296-37805-5-ND"))
      (libsource (lib "SyTungNguyen") (part "AM3358BZCZ100"))
    )
    (comp (ref "U11")
      (value "SN74LVC2G34DCKR")
      (footprint "DCK0006A_L")
      (description "Dual Buffer Gate, DCK0006A, LARGE T&R")
      (fields
        (field (name "MANUFACTURER") "Texas Instruments")
        (field (name "GENERIC PART NUMBER") "SN74LVC2G34")
      )
      (libsource (lib "Altium Content Vault") (part "TI-SN74XXX2GXXX-6_A"))
    )
    (comp (ref "X2")
      (value "TSX-3225 24.0000MF15X-AC3")
      (footprint "FP-NX3225SA-MFG")
      (description "MHz Range Crystal, 24 MHz, -40 to 85 degC, 4-Pin SMD, RoHS, Tape and Reel")
      (fields (field (name "TOLERANCE") "10PPM") (field (name "MANUFACTURER") "Epson"))
      (libsource (lib "AM3358_DEV_BOARD") (part "XTAL-1-3-4"))
    )
    (comp (ref "Y1")
      (value "ABS07-120-32.768KHZ-T")
      (footprint "ABRA-ABS07_A_V")
      (description "Tuning Fork Crystal, 32.768 KHz, +/- 20 ppm, -40 to 85 degC, 2-Pin SMD, RoHS, Tape and Reel")
      (fields (field (name "MANUFACTURER") "Abracon") (field (name "TOLERANCE") "20ppm"))
      (libsource (lib "Altium Content Vault") (part "XTAL-1-2-2"))
    )
  )
  (nets
    (net (code "1") (name "/EMU2") (class "Default")
      (node (ref "U1") (pin "A15") (pinfunction "XDMA_EVENT_INTR0_A15") (pintype "input"))
    )
    (net (code "2") (name "/PMIC_INT") (class "Default")
      (node (ref "U1") (pin "B18") (pinfunction "EXTINTN_B18") (pintype "input"))
    )
    (net (code "3") (name "/PMIC_LDO_PGOOD") (class "Default")
      (node (ref "U1") (pin "B5") (pinfunction "RTC_PWRONRSTN_B5") (pintype "input"))
    )
    (net (code "4") (name "/PMIC_PGOOD") (class "Default")
      (node (ref "U1") (pin "B15") (pinfunction "PWRONRSTN_B15") (pintype "input"))
      (node (ref "U11") (pin "3") (pinfunction "2A_3") (pintype "input"))
    )
    (net (code "5") (name "/PMIC_POWER_EN") (class "Default")
      (node (ref "U1") (pin "C6") (pinfunction "PMIC_POWER_EN_C6") (pintype "output"))
    )
    (net (code "6") (name "/PMIC_WAKEUP") (class "Default")
      (node (ref "R4") (pin "2") (pinfunction "2_2") (pintype "passive"))
      (node (ref "U1") (pin "C5") (pinfunction "EXT_WAKEUP_C5") (pintype "input"))
    )
    (net (code "7") (name "/PWM0_OUT") (class "Default")
      (node (ref "U1") (pin "C18") (pinfunction "ECAP0_IN_PWM0_OUT_C18") (pintype "bidirectional"))
    )
    (net (code "8") (name "/SYS_RST") (class "Default")
      (node (ref "C154") (pin "2") (pinfunction "2_2") (pintype "passive"))
      (node (ref "R6") (pin "1") (pinfunction "1_1") (pintype "passive"))
      (node (ref "U1") (pin "A10") (pinfunction "WARMRSTN_A10") (pintype "bidirectional"))
      (node (ref "U11") (pin "4") (pinfunction "2Y_4") (pintype "output"))
      (node (ref "U11") (pin "6") (pinfunction "1Y_6") (pintype "output"))
    )
    (net (code "9") (name "/USB1_VBUS") (class "Default")
      (node (ref "U1") (pin "T18") (pinfunction "USB1_VBUS_T18") (pintype "power_in"))
    )
    (net (code "10") (name "/VDD_MPUON") (class "Default")
      (node (ref "TP1") (pin "1") (pintype "passive"))
      (node (ref "U1") (pin "A2") (pinfunction "VDD_MPU_MON_A2") (pintype "power_in"))
    )
    (net (code "11") (name "/WL_EXT_32K") (class "Default")
      (node (ref "U1") (pin "D14") (pinfunction "XDMA_EVENT_INTR1_D14") (pintype "input"))
    )
    (net (code "12") (name "AGND") (class "Default")
      (node (ref "C105") (pin "1") (pinfunction "1_1") (pintype "passive"))
      (node (ref "C106") (pin "1") (pinfunction "1_1") (pintype "passive"))
      (node (ref "C107") (pin "1") (pinfunction "1_1") (pintype "passive"))
      (node (ref "C98") (pin "1") (pinfunction "1_1") (pintype "passive"))
      (node (ref "FB1") (pin "1") (pinfunction "1_1") (pintype "passive"))
      (node (ref "U1") (pin "A9") (pinfunction "VREFN_A9") (pintype "power_in"))
      (node (ref "U1") (pin "E8") (pinfunction "VSSA_ADC_E8") (pintype "passive"))
    )
    (net (code "13") (name "GND") (class "Default")
      (node (ref "C1") (pin "1") (pinfunction "1_1") (pintype "passive"))
      (node (ref "C10") (pin "1") (pinfunction "1_1") (pintype "passive"))
      (node (ref "C100") (pin "1") (pinfunction "1_1") (pintype "passive"))
      (node (ref "C101") (pin "1") (pinfunction "1_1") (pintype "passive"))
      (node (ref "C102") (pin "1") (pinfunction "1_1") (pintype "passive"))
      (node (ref "C103") (pin "1") (pinfunction "1_1") (pintype "passive"))
      (node (ref "C104") (pin "1") (pinfunction "1_1") (pintype "passive"))
      (node (ref "C108") (pin "1") (pinfunction "1_1") (pintype "passive"))
      (node (ref "C109") (pin "1") (pinfunction "1_1") (pintype "passive"))
      (node (ref "C11") (pin "1") (pinfunction "1_1") (pintype "passive"))
      (node (ref "C110") (pin "1") (pinfunction "1_1") (pintype "passive"))
      (node (ref "C111") (pin "1") (pinfunction "1_1") (pintype "passive"))
      (node (ref "C112") (pin "1") (pinfunction "1_1") (pintype "passive"))
      (node (ref "C113") (pin "1") (pinfunction "1_1") (pintype "passive"))
      (node (ref "C12") (pin "1") (pinfunction "1_1") (pintype "passive"))
      (node (ref "C13") (pin "1") (pinfunction "1_1") (pintype "passive"))
      (node (ref "C14") (pin "1") (pinfunction "1_1") (pintype "passive"))
      (node (ref "C15") (pin "1") (pinfunction "1_1") (pintype "passive"))
      (node (ref "C153") (pin "1") (pinfunction "1_1") (pintype "passive"))
      (node (ref "C154") (pin "1") (pinfunction "1_1") (pintype "passive"))
      (node (ref "C16") (pin "1") (pinfunction "1_1") (pintype "passive"))
      (node (ref "C17") (pin "1") (pinfunction "1_1") (pintype "passive"))
      (node (ref "C18") (pin "1") (pinfunction "1_1") (pintype "passive"))
      (node (ref "C19") (pin "1") (pinfunction "1_1") (pintype "passive"))
      (node (ref "C2") (pin "1") (pinfunction "1_1") (pintype "passive"))
      (node (ref "C20") (pin "1") (pinfunction "1_1") (pintype "passive"))
      (node (ref "C21") (pin "1") (pinfunction "1_1") (pintype "passive"))
      (node (ref "C22") (pin "1") (pinfunction "1_1") (pintype "passive"))
      (node (ref "C23") (pin "1") (pinfunction "1_1") (pintype "passive"))
      (node (ref "C24") (pin "1") (pinfunction "1_1") (pintype "passive"))
      (node (ref "C25") (pin "1") (pinfunction "1_1") (pintype "passive"))
      (node (ref "C26") (pin "1") (pinfunction "1_1") (pintype "passive"))
      (node (ref "C27") (pin "1") (pinfunction "1_1") (pintype "passive"))
      (node (ref "C28") (pin "1") (pinfunction "1_1") (pintype "passive"))
      (node (ref "C29") (pin "1") (pinfunction "1_1") (pintype "passive"))
      (node (ref "C3") (pin "1") (pinfunction "1_1") (pintype "passive"))
      (node (ref "C30") (pin "1") (pinfunction "1_1") (pintype "passive"))
      (node (ref "C31") (pin "1") (pinfunction "1_1") (pintype "passive"))
      (node (ref "C32") (pin "1") (pinfunction "1_1") (pintype "passive"))
      (node (ref "C33") (pin "1") (pinfunction "1_1") (pintype "passive"))
      (node (ref "C34") (pin "1") (pinfunction "1_1") (pintype "passive"))
      (node (ref "C35") (pin "1") (pinfunction "1_1") (pintype "passive"))
      (node (ref "C36") (pin "1") (pinfunction "1_1") (pintype "passive"))
      (node (ref "C37") (pin "1") (pinfunction "1_1") (pintype "passive"))
      (node (ref "C38") (pin "1") (pinfunction "1_1") (pintype "passive"))
      (node (ref "C39") (pin "1") (pinfunction "1_1") (pintype "passive"))
      (node (ref "C4") (pin "1") (pinfunction "1_1") (pintype "passive"))
      (node (ref "C40") (pin "1") (pinfunction "1_1") (pintype "passive"))
      (node (ref "C41") (pin "1") (pinfunction "1_1") (pintype "passive"))
      (node (ref "C42") (pin "1") (pinfunction "1_1") (pintype "passive"))
      (node (ref "C43") (pin "1") (pinfunction "1_1") (pintype "passive"))
      (node (ref "C44") (pin "1") (pinfunction "1_1") (pintype "passive"))
      (node (ref "C45") (pin "1") (pinfunction "1_1") (pintype "passive"))
      (node (ref "C46") (pin "1") (pinfunction "1_1") (pintype "passive"))
      (node (ref "C47") (pin "1") (pinfunction "1_1") (pintype "passive"))
      (node (ref "C48") (pin "1") (pinfunction "1_1") (pintype "passive"))
      (node (ref "C49") (pin "1") (pinfunction "1_1") (pintype "passive"))
      (node (ref "C5") (pin "1") (pinfunction "1_1") (pintype "passive"))
      (node (ref "C6") (pin "1") (pinfunction "1_1") (pintype "passive"))
      (node (ref "C7") (pin "1") (pinfunction "1_1") (pintype "passive"))
      (node (ref "C70") (pin "1") (pinfunction "1_1") (pintype "passive"))
      (node (ref "C8") (pin "1") (pinfunction "1_1") (pintype "passive"))
      (node (ref "C83") (pin "1") (pinfunction "1_1") (pintype "passive"))
      (node (ref "C84") (pin "1") (pinfunction "1_1") (pintype "passive"))
      (node (ref "C9") (pin "1") (pinfunction "1_1") (pintype "passive"))
      (node (ref "C90") (pin "1") (pinfunction "1_1") (pintype "passive"))
      (node (ref "C91") (pin "1") (pinfunction "1_1") (pintype "passive"))
      (node (ref "C92") (pin "1") (pinfunction "1_1") (pintype "passive"))
      (node (ref "C93") (pin "1") (pinfunction "1_1") (pintype "passive"))
      (node (ref "C94") (pin "1") (pinfunction "1_1") (pintype "passive"))
      (node (ref "C95") (pin "1") (pinfunction "1_1") (pintype "passive"))
      (node (ref "C96") (pin "1") (pinfunction "1_1") (pintype "passive"))
      (node (ref "C97") (pin "1") (pinfunction "1_1") (pintype "passive"))
      (node (ref "C99") (pin "1") (pinfunction "1_1") (pintype "passive"))
      (node (ref "FB1") (pin "2") (pinfunction "2_2") (pintype "passive"))
      (node (ref "R7") (pin "1") (pinfunction "1_1") (pintype "passive"))
      (node (ref "R76") (pin "1") (pinfunction "1_1") (pintype "passive"))
      (node (ref "R9") (pin "1") (pinfunction "1_1") (pintype "passive"))
      (node (ref "SW1") (pin "3") (pinfunction "3_3") (pintype "passive"))
      (node (ref "SW1") (pin "4") (pinfunction "4_4") (pintype "passive"))
      (node (ref "U1") (pin "A1") (pinfunction "VSS_A1") (pintype "passive"))
      (node (ref "U1") (pin "A18") (pinfunction "VSS_A18") (pintype "passive"))
      (node (ref "U1") (pin "F8") (pinfunction "VSS_F8") (pintype "passive"))
      (node (ref "U1") (pin "G11") (pinfunction "VSS_G11") (pintype "passive"))
      (node (ref "U1") (pin "G12") (pinfunction "VSS_G12") (pintype "passive"))
      (node (ref "U1") (pin "G8") (pinfunction "VSS_G8") (pintype "passive"))
      (node (ref "U1") (pin "G9") (pinfunction "VSS_G9") (pintype "passive"))
      (node (ref "U1") (pin "H10") (pinfunction "VSS_H10") (pintype "passive"))
      (node (ref "U1") (pin "H12") (pinfunction "VSS_H12") (pintype "passive"))
      (node (ref "U1") (pin "H6") (pinfunction "VSS_H6") (pintype "passive"))
      (node (ref "U1") (pin "H7") (pinfunction "VSS_H7") (pintype "passive"))
      (node (ref "U1") (pin "H8") (pinfunction "VSS_H8") (pintype "passive"))
      (node (ref "U1") (pin "H9") (pinfunction "VSS_H9") (pintype "passive"))
      (node (ref "U1") (pin "J10") (pinfunction "VSS_J10") (pintype "passive"))
      (node (ref "U1") (pin "J11") (pinfunction "VSS_J11") (pintype "passive"))
      (node (ref "U1") (pin "J6") (pinfunction "VSS_J6") (pintype "passive"))
      (node (ref "U1") (pin "J7") (pinfunction "VSS_J7") (pintype "passive"))
      (node (ref "U1") (pin "J8") (pinfunction "VSS_J8") (pintype "passive"))
      (node (ref "U1") (pin "J9") (pinfunction "VSS_J9") (pintype "passive"))
      (node (ref "U1") (pin "K10") (pinfunction "VSS_K10") (pintype "passive"))
      (node (ref "U1") (pin "K11") (pinfunction "VSS_K11") (pintype "passive"))
      (node (ref "U1") (pin "K7") (pinfunction "VSS_K7") (pintype "passive"))
      (node (ref "U1") (pin "K9") (pinfunction "VSS_K9") (pintype "passive"))
      (node (ref "U1") (pin "L10") (pinfunction "VSS_L10") (pintype "passive"))
      (node (ref "U1") (pin "L11") (pinfunction "VSS_L11") (pintype "passive"))
      (node (ref "U1") (pin "L12") (pinfunction "VSS_L12") (pintype "passive"))
      (node (ref "U1") (pin "L13") (pinfunction "VSS_L13") (pintype "passive"))
      (node (ref "U1") (pin "M10") (pinfunction "VSS_M10") (pintype "passive"))
      (node (ref "U1") (pin "M12") (pinfunction "VSS_M12") (pintype "passive"))
      (node (ref "U1") (pin "M14") (pinfunction "VSSA_USB_M14") (pintype "passive"))
      (node (ref "U1") (pin "M6") (pinfunction "VSS_M6") (pintype "passive"))
      (node (ref "U1") (pin "M7") (pinfunction "VSS_M7") (pintype "passive"))
      (node (ref "U1") (pin "M8") (pinfunction "VSS_M8") (pintype "passive"))
      (node (ref "U1") (pin "M9") (pinfunction "VSS_M9") (pintype "passive"))
      (node (ref "U1") (pin "N10") (pinfunction "VSS_N10") (pintype "passive"))
      (node (ref "U1") (pin "N11") (pinfunction "VSS_N11") (pintype "passive"))
      (node (ref "U1") (pin "N14") (pinfunction "VSSA_USB_N14") (pintype "passive"))
      (node (ref "U1") (pin "N7") (pinfunction "VSS_N7") (pintype "passive"))
      (node (ref "U1") (pin "V1") (pinfunction "VSS_V1") (pintype "passive"))
      (node (ref "U1") (pin "V18") (pinfunction "VSS_V18") (pintype "passive"))
      (node (ref "U11") (pin "2") (pinfunction "GND_2") (pintype "power_in"))
    )
    (net (code "14") (name "GND_OSC") (class "Default")
      (node (ref "C156") (pin "1") (pinfunction "1_1") (pintype "passive"))
      (node (ref "C158") (pin "1") (pinfunction "1_1") (pintype "passive"))
      (node (ref "R75") (pin "1") (pinfunction "1_1") (pintype "passive"))
      (node (ref "R76") (pin "2") (pinfunction "2_2") (pintype "passive"))
      (node (ref "U1") (pin "V11") (pinfunction "VSS_OSC_V11") (pintype "passive"))
      (node (ref "X2") (pin "2") (pinfunction "GND_2") (pintype "power_in"))
      (node (ref "X2") (pin "4") (pinfunction "GND_4") (pintype "power_in"))
    )
    (net (code "15") (name "GND_RTC") (class "Default")
      (node (ref "C155") (pin "1") (pinfunction "1_1") (pintype "passive"))
      (node (ref "C157") (pin "1") (pinfunction "1_1") (pintype "passive"))
      (node (ref "R75") (pin "2") (pinfunction "2_2") (pintype "passive"))
      (node (ref "U1") (pin "A5") (pinfunction "VSS_RTC_A5") (pintype "passive"))
    )
    (net (code "16") (name "Net-(U1G-RTC_KALDO_ENN)") (class "Default")
      (node (ref "R7") (pin "2") (pinfunction "2_2") (pintype "passive"))
      (node (ref "U1") (pin "B4") (pinfunction "RTC_KALDO_ENN_B4") (pintype "input"))
    )
    (net (code "17") (name "Net-(U1G-RTC_XTALIN)") (class "Default")
      (node (ref "C157") (pin "2") (pinfunction "2_2") (pintype "passive"))
      (node (ref "U1") (pin "A6") (pinfunction "RTC_XTALIN_A6") (pintype "input"))
      (node (ref "Y1") (pin "2") (pinfunction "2_2") (pintype "passive"))
    )
    (net (code "18") (name "Net-(U1G-RTC_XTALOUT)") (class "Default")
      (node (ref "C155") (pin "2") (pinfunction "2_2") (pintype "passive"))
      (node (ref "U1") (pin "A4") (pinfunction "RTC_XTALOUT_A4") (pintype "output"))
      (node (ref "Y1") (pin "1") (pinfunction "1_1") (pintype "passive"))
    )
    (net (code "19") (name "Net-(U1G-XTALIN)") (class "Default")
      (node (ref "C158") (pin "2") (pinfunction "2_2") (pintype "passive"))
      (node (ref "R74") (pin "2") (pinfunction "2_2") (pintype "passive"))
      (node (ref "U1") (pin "V10") (pinfunction "XTALIN_V10") (pintype "input"))
      (node (ref "X2") (pin "1") (pinfunction "X1_1") (pintype "passive"))
    )
    (net (code "20") (name "Net-(U1G-XTALOUT)") (class "Default")
      (node (ref "C156") (pin "2") (pinfunction "2_2") (pintype "passive"))
      (node (ref "R74") (pin "1") (pinfunction "1_1") (pintype "passive"))
      (node (ref "U1") (pin "U11") (pinfunction "XTALOUT_U11") (pintype "output"))
      (node (ref "X2") (pin "3") (pinfunction "X2_3") (pintype "passive"))
    )
    (net (code "21") (name "Net-(U1H-CAP_VBB_MPU)") (class "Default")
      (node (ref "C110") (pin "2") (pinfunction "2_2") (pintype "passive"))
      (node (ref "U1") (pin "C10") (pinfunction "CAP_VBB_MPU_C10") (pintype "passive"))
    )
    (net (code "22") (name "Net-(U1H-CAP_VDD_RTC)") (class "Default")
      (node (ref "C111") (pin "2") (pinfunction "2_2") (pintype "passive"))
      (node (ref "U1") (pin "D6") (pinfunction "CAP_VDD_RTC_D6") (pintype "passive"))
    )
    (net (code "23") (name "Net-(U1H-CAP_VDD_SRAM_CORE)") (class "Default")
      (node (ref "C112") (pin "2") (pinfunction "2_2") (pintype "passive"))
      (node (ref "U1") (pin "D9") (pinfunction "CAP_VDD_SRAM_CORE_D9") (pintype "passive"))
    )
    (net (code "24") (name "Net-(U1H-CAP_VDD_SRAM_MPU)") (class "Default")
      (node (ref "C113") (pin "2") (pinfunction "2_2") (pintype "passive"))
      (node (ref "U1") (pin "D11") (pinfunction "CAP_VDD_SRAM_MPU_D11") (pintype "passive"))
    )
    (net (code "25") (name "Net-(U1H-DDR_VTP)") (class "Default")
      (node (ref "R9") (pin "2") (pinfunction "2_2") (pintype "passive"))
      (node (ref "U1") (pin "J3") (pinfunction "DDR_VTP_J3") (pintype "power_in"))
    )
    (net (code "26") (name "Net-(U1H-RESERVED)") (class "Default")
      (node (ref "TP2") (pin "1") (pintype "passive"))
      (node (ref "U1") (pin "A3") (pinfunction "RESERVED_A3") (pintype "passive"))
    )
    (net (code "27") (name "Net-(U1H-VREFP)") (class "Default")
      (node (ref "C105") (pin "2") (pinfunction "2_2") (pintype "passive"))
      (node (ref "C106") (pin "2") (pinfunction "2_2") (pintype "passive"))
      (node (ref "C107") (pin "2") (pinfunction "2_2") (pintype "passive"))
      (node (ref "R8") (pin "1") (pinfunction "1_1") (pintype "passive"))
      (node (ref "U1") (pin "B9") (pinfunction "VREFP_B9") (pintype "power_in"))
    )
    (net (code "28") (name "Net-(U11A-1A)") (class "Default")
      (node (ref "R5") (pin "2") (pinfunction "2_2") (pintype "passive"))
      (node (ref "SW1") (pin "1") (pinfunction "1_1") (pintype "passive"))
      (node (ref "SW1") (pin "2") (pinfunction "2_2") (pintype "passive"))
      (node (ref "U11") (pin "1") (pinfunction "1A_1") (pintype "input"))
    )
    (net (code "29") (name "VDDS") (class "Default")
      (node (ref "C42") (pin "2") (pinfunction "2_2") (pintype "passive"))
      (node (ref "C43") (pin "2") (pinfunction "2_2") (pintype "passive"))
      (node (ref "C44") (pin "2") (pinfunction "2_2") (pintype "passive"))
      (node (ref "C45") (pin "2") (pinfunction "2_2") (pintype "passive"))
      (node (ref "C46") (pin "2") (pinfunction "2_2") (pintype "passive"))
      (node (ref "C47") (pin "2") (pinfunction "2_2") (pintype "passive"))
      (node (ref "C48") (pin "2") (pinfunction "2_2") (pintype "passive"))
      (node (ref "C49") (pin "2") (pinfunction "2_2") (pintype "passive"))
      (node (ref "U1") (pin "E14") (pinfunction "VDDS_E14") (pintype "power_in"))
      (node (ref "U1") (pin "E6") (pinfunction "VDDS_E6") (pintype "power_in"))
      (node (ref "U1") (pin "F9") (pinfunction "VDDS_F9") (pintype "power_in"))
      (node (ref "U1") (pin "K13") (pinfunction "VDDS_K13") (pintype "power_in"))
      (node (ref "U1") (pin "N6") (pinfunction "VDDS_N6") (pintype "power_in"))
      (node (ref "U1") (pin "P14") (pinfunction "VDDS_P14") (pintype "power_in"))
      (node (ref "U1") (pin "P9") (pinfunction "VDDS_P9") (pintype "power_in"))
    )
    (net (code "30") (name "VDDS_DDR_1V35") (class "Default")
      (node (ref "C16") (pin "2") (pinfunction "2_2") (pintype "passive"))
      (node (ref "C31") (pin "2") (pinfunction "2_2") (pintype "passive"))
      (node (ref "C32") (pin "2") (pinfunction "2_2") (pintype "passive"))
      (node (ref "C70") (pin "2") (pinfunction "2_2") (pintype "passive"))
      (node (ref "C83") (pin "2") (pinfunction "2_2") (pintype "passive"))
      (node (ref "C84") (pin "2") (pinfunction "2_2") (pintype "passive"))
      (node (ref "U1") (pin "E5") (pinfunction "VDDS_DDR_E5") (pintype "power_in"))
      (node (ref "U1") (pin "F5") (pinfunction "VDDS_DDR_F5") (pintype "power_in"))
      (node (ref "U1") (pin "G5") (pinfunction "VDDS_DDR_G5") (pintype "power_in"))
      (node (ref "U1") (pin "H5") (pinfunction "VDDS_DDR_H5") (pintype "power_in"))
      (node (ref "U1") (pin "J5") (pinfunction "VDDS_DDR_J5") (pintype "power_in"))
      (node (ref "U1") (pin "K5") (pinfunction "VDDS_DDR_K5") (pintype "power_in"))
      (node (ref "U1") (pin "L5") (pinfunction "VDDS_DDR_L5") (pintype "power_in"))
    )
    (net (code "31") (name "VDD_1V8") (class "Default")
      (node (ref "C93") (pin "2") (pinfunction "2_2") (pintype "passive"))
      (node (ref "C94") (pin "2") (pinfunction "2_2") (pintype "passive"))
      (node (ref "C95") (pin "2") (pinfunction "2_2") (pintype "passive"))
      (node (ref "C96") (pin "2") (pinfunction "2_2") (pintype "passive"))
      (node (ref "C97") (pin "2") (pinfunction "2_2") (pintype "passive"))
      (node (ref "FB2") (pin "1") (pinfunction "1_1") (pintype "passive"))
      (node (ref "FB3") (pin "1") (pinfunction "1_1") (pintype "passive"))
      (node (ref "U1") (pin "D10") (pinfunction "VDDS_SRAM_MPU_BB_D10") (pintype "power_in"))
      (node (ref "U1") (pin "E9") (pinfunction "VDDS_SRAM_CORE_BG_E9") (pintype "power_in"))
      (node (ref "U1") (pin "N16") (pinfunction "VDDA1P8V_USB0_N16") (pintype "power_in"))
      (node (ref "U1") (pin "R16") (pinfunction "VDDA1P8V_USB1_R16") (pintype "power_in"))
    )
    (net (code "32") (name "VDD_3V3A") (class "Default")
      (node (ref "C103") (pin "2") (pinfunction "2_2") (pintype "passive"))
      (node (ref "C104") (pin "2") (pinfunction "2_2") (pintype "passive"))
      (node (ref "C153") (pin "2") (pinfunction "2_2") (pintype "passive"))
      (node (ref "C17") (pin "2") (pinfunction "2_2") (pintype "passive"))
      (node (ref "C18") (pin "2") (pinfunction "2_2") (pintype "passive"))
      (node (ref "C19") (pin "2") (pinfunction "2_2") (pintype "passive"))
      (node (ref "C20") (pin "2") (pinfunction "2_2") (pintype "passive"))
      (node (ref "C21") (pin "2") (pinfunction "2_2") (pintype "passive"))
      (node (ref "C22") (pin "2") (pinfunction "2_2") (pintype "passive"))
      (node (ref "C23") (pin "2") (pinfunction "2_2") (pintype "passive"))
      (node (ref "C24") (pin "2") (pinfunction "2_2") (pintype "passive"))
      (node (ref "C25") (pin "2") (pinfunction "2_2") (pintype "passive"))
      (node (ref "C26") (pin "2") (pinfunction "2_2") (pintype "passive"))
      (node (ref "C33") (pin "2") (pinfunction "2_2") (pintype "passive"))
      (node (ref "C34") (pin "2") (pinfunction "2_2") (pintype "passive"))
      (node (ref "C35") (pin "2") (pinfunction "2_2") (pintype "passive"))
      (node (ref "C36") (pin "2") (pinfunction "2_2") (pintype "passive"))
      (node (ref "C37") (pin "2") (pinfunction "2_2") (pintype "passive"))
      (node (ref "C38") (pin "2") (pinfunction "2_2") (pintype "passive"))
      (node (ref "C39") (pin "2") (pinfunction "2_2") (pintype "passive"))
      (node (ref "C40") (pin "2") (pinfunction "2_2") (pintype "passive"))
      (node (ref "C41") (pin "2") (pinfunction "2_2") (pintype "passive"))
      (node (ref "C92") (pin "2") (pinfunction "2_2") (pintype "passive"))
      (node (ref "R5") (pin "1") (pinfunction "1_1") (pintype "passive"))
      (node (ref "R6") (pin "2") (pinfunction "2_2") (pintype "passive"))
      (node (ref "U1") (pin "E10") (pinfunction "VDDSHV6_E10") (pintype "power_in"))
      (node (ref "U1") (pin "E11") (pinfunction "VDDSHV6_E11") (pintype "power_in"))
      (node (ref "U1") (pin "E12") (pinfunction "VDDSHV6_E12") (pintype "power_in"))
      (node (ref "U1") (pin "E13") (pinfunction "VDDSHV6_E13") (pintype "power_in"))
      (node (ref "U1") (pin "F14") (pinfunction "VDDSHV6_F14") (pintype "power_in"))
      (node (ref "U1") (pin "G14") (pinfunction "VDDSHV6_G14") (pintype "power_in"))
      (node (ref "U1") (pin "H14") (pinfunction "VDDSHV4_H14") (pintype "power_in"))
      (node (ref "U1") (pin "J14") (pinfunction "VDDSHV4_J14") (pintype "power_in"))
      (node (ref "U1") (pin "K14") (pinfunction "VDDSHV5_K14") (pintype "power_in"))
      (node (ref "U1") (pin "L14") (pinfunction "VDDSHV5_L14") (pintype "power_in"))
      (node (ref "U1") (pin "N15") (pinfunction "VDDA3P3V_USB0_N15") (pintype "power_in"))
      (node (ref "U1") (pin "N5") (pinfunction "VDDSHV6_N5") (pintype "power_in"))
      (node (ref "U1") (pin "P10") (pinfunction "VDDSHV2_P10") (pintype "power_in"))
      (node (ref "U1") (pin "P11") (pinfunction "VDDSHV2_P11") (pintype "power_in"))
      (node (ref "U1") (pin "P12") (pinfunction "VDDSHV3_P12") (pintype "power_in"))
      (node (ref "U1") (pin "P13") (pinfunction "VDDSHV3_P13") (pintype "power_in"))
      (node (ref "U1") (pin "P5") (pinfunction "VDDSHV6_P5") (pintype "power_in"))
      (node (ref "U1") (pin "P6") (pinfunction "VDDSHV6_P6") (pintype "power_in"))
      (node (ref "U1") (pin "P7") (pinfunction "VDDSHV1_P7") (pintype "power_in"))
      (node (ref "U1") (pin "P8") (pinfunction "VDDSHV1_P8") (pintype "power_in"))
      (node (ref "U1") (pin "R15") (pinfunction "VDDA3P3V_USB1_R15") (pintype "power_in"))
      (node (ref "U11") (pin "5") (pinfunction "VCC_5") (pintype "power_in"))
    )
    (net (code "33") (name "VDD_ADC") (class "Default")
      (node (ref "C98") (pin "2") (pinfunction "2_2") (pintype "passive"))
      (node (ref "FB2") (pin "2") (pinfunction "2_2") (pintype "passive"))
      (node (ref "R8") (pin "2") (pinfunction "2_2") (pintype "passive"))
      (node (ref "U1") (pin "D8") (pinfunction "VDDA_ADC_D8") (pintype "power_in"))
    )
    (net (code "34") (name "VDD_CORE") (class "Default")
      (node (ref "C1") (pin "2") (pinfunction "2_2") (pintype "passive"))
      (node (ref "C10") (pin "2") (pinfunction "2_2") (pintype "passive"))
      (node (ref "C11") (pin "2") (pinfunction "2_2") (pintype "passive"))
      (node (ref "C12") (pin "2") (pinfunction "2_2") (pintype "passive"))
      (node (ref "C13") (pin "2") (pinfunction "2_2") (pintype "passive"))
      (node (ref "C14") (pin "2") (pinfunction "2_2") (pintype "passive"))
      (node (ref "C15") (pin "2") (pinfunction "2_2") (pintype "passive"))
      (node (ref "C2") (pin "2") (pinfunction "2_2") (pintype "passive"))
      (node (ref "C3") (pin "2") (pinfunction "2_2") (pintype "passive"))
      (node (ref "C4") (pin "2") (pinfunction "2_2") (pintype "passive"))
      (node (ref "C5") (pin "2") (pinfunction "2_2") (pintype "passive"))
      (node (ref "C6") (pin "2") (pinfunction "2_2") (pintype "passive"))
      (node (ref "C7") (pin "2") (pinfunction "2_2") (pintype "passive"))
      (node (ref "C8") (pin "2") (pinfunction "2_2") (pintype "passive"))
      (node (ref "C9") (pin "2") (pinfunction "2_2") (pintype "passive"))
      (node (ref "C90") (pin "2") (pinfunction "2_2") (pintype "passive"))
      (node (ref "U1") (pin "F6") (pinfunction "VDD_CORE_F6") (pintype "power_in"))
      (node (ref "U1") (pin "F7") (pinfunction "VDD_CORE_F7") (pintype "power_in"))
      (node (ref "U1") (pin "G10") (pinfunction "VDD_CORE_G10") (pintype "power_in"))
      (node (ref "U1") (pin "G6") (pinfunction "VDD_CORE_G6") (pintype "power_in"))
      (node (ref "U1") (pin "G7") (pinfunction "VDD_CORE_G7") (pintype "power_in"))
      (node (ref "U1") (pin "H11") (pinfunction "VDD_CORE_H11") (pintype "power_in"))
      (node (ref "U1") (pin "J12") (pinfunction "VDD_CORE_J12") (pintype "power_in"))
      (node (ref "U1") (pin "K12") (pinfunction "VDD_CORE_K12") (pintype "power_in"))
      (node (ref "U1") (pin "K6") (pinfunction "VDD_CORE_K6") (pintype "power_in"))
      (node (ref "U1") (pin "K8") (pinfunction "VDD_CORE_K8") (pintype "power_in"))
      (node (ref "U1") (pin "L6") (pinfunction "VDD_CORE_L6") (pintype "power_in"))
      (node (ref "U1") (pin "L7") (pinfunction "VDD_CORE_L7") (pintype "power_in"))
      (node (ref "U1") (pin "L8") (pinfunction "VDD_CORE_L8") (pintype "power_in"))
      (node (ref "U1") (pin "L9") (pinfunction "VDD_CORE_L9") (pintype "power_in"))
      (node (ref "U1") (pin "M11") (pinfunction "VDD_CORE_M11") (pintype "power_in"))
      (node (ref "U1") (pin "M13") (pinfunction "VDD_CORE_M13") (pintype "power_in"))
      (node (ref "U1") (pin "N12") (pinfunction "VDD_CORE_N12") (pintype "power_in"))
      (node (ref "U1") (pin "N13") (pinfunction "VDD_CORE_N13") (pintype "power_in"))
      (node (ref "U1") (pin "N8") (pinfunction "VDD_CORE_N8") (pintype "power_in"))
      (node (ref "U1") (pin "N9") (pinfunction "VDD_CORE_N9") (pintype "power_in"))
    )
    (net (code "35") (name "VDD_MPU") (class "Default")
      (node (ref "C27") (pin "2") (pinfunction "2_2") (pintype "passive"))
      (node (ref "C28") (pin "2") (pinfunction "2_2") (pintype "passive"))
      (node (ref "C29") (pin "2") (pinfunction "2_2") (pintype "passive"))
      (node (ref "C30") (pin "2") (pinfunction "2_2") (pintype "passive"))
      (node (ref "C91") (pin "2") (pinfunction "2_2") (pintype "passive"))
      (node (ref "U1") (pin "F10") (pinfunction "VDD_MPU_F10") (pintype "power_in"))
      (node (ref "U1") (pin "F11") (pinfunction "VDD_MPU_F11") (pintype "power_in"))
      (node (ref "U1") (pin "F12") (pinfunction "VDD_MPU_F12") (pintype "power_in"))
      (node (ref "U1") (pin "F13") (pinfunction "VDD_MPU_F13") (pintype "power_in"))
      (node (ref "U1") (pin "G13") (pinfunction "VDD_MPU_G13") (pintype "power_in"))
      (node (ref "U1") (pin "H13") (pinfunction "VDD_MPU_H13") (pintype "power_in"))
      (node (ref "U1") (pin "J13") (pinfunction "VDD_MPU_J13") (pintype "power_in"))
    )
    (net (code "36") (name "VDD_PLL") (class "Default")
      (node (ref "C100") (pin "2") (pinfunction "2_2") (pintype "passive"))
      (node (ref "C101") (pin "2") (pinfunction "2_2") (pintype "passive"))
      (node (ref "C102") (pin "2") (pinfunction "2_2") (pintype "passive"))
      (node (ref "C99") (pin "2") (pinfunction "2_2") (pintype "passive"))
      (node (ref "FB3") (pin "2") (pinfunction "2_2") (pintype "passive"))
      (node (ref "U1") (pin "E7") (pinfunction "VDDS_PLL_DDR_E7") (pintype "power_in"))
      (node (ref "U1") (pin "H15") (pinfunction "VDDS_PLL_MPU_H15") (pintype "power_in"))
      (node (ref "U1") (pin "R10") (pinfunction "VDDS_PLL_CORE_LCD_R10") (pintype "power_in"))
      (node (ref "U1") (pin "R11") (pinfunction "VDDS_OSC_R11") (pintype "power_in"))
    )
    (net (code "37") (name "VREF_DDR_0V675") (class "Default")
      (node (ref "C109") (pin "2") (pinfunction "2_2") (pintype "passive"))
      (node (ref "U1") (pin "J4") (pinfunction "DDR_VREF_J4") (pintype "power_in"))
    )
    (net (code "38") (name "VRTC") (class "Default")
      (node (ref "C108") (pin "2") (pinfunction "2_2") (pintype "passive"))
      (node (ref "R4") (pin "1") (pinfunction "1_1") (pintype "passive"))
      (node (ref "U1") (pin "D7") (pinfunction "VDDS_RTC_D7") (pintype "power_in"))
    )
    (net (code "39") (name "unconnected-(U1H-USB0_VBUS-PadP15)") (class "Default")
      (node (ref "U1") (pin "P15") (pinfunction "USB0_VBUS_P15") (pintype "power_in+no_connect"))
    )
    (net (code "40") (name "unconnected-(U1H-VPP-PadM5)") (class "Default")
      (node (ref "U1") (pin "M5") (pinfunction "VPP_M5") (pintype "power_in+no_connect"))
    )
  )
)
